# Mini_Control_Board.net
KiCad netlist of a schematic drawn in Altium Designer
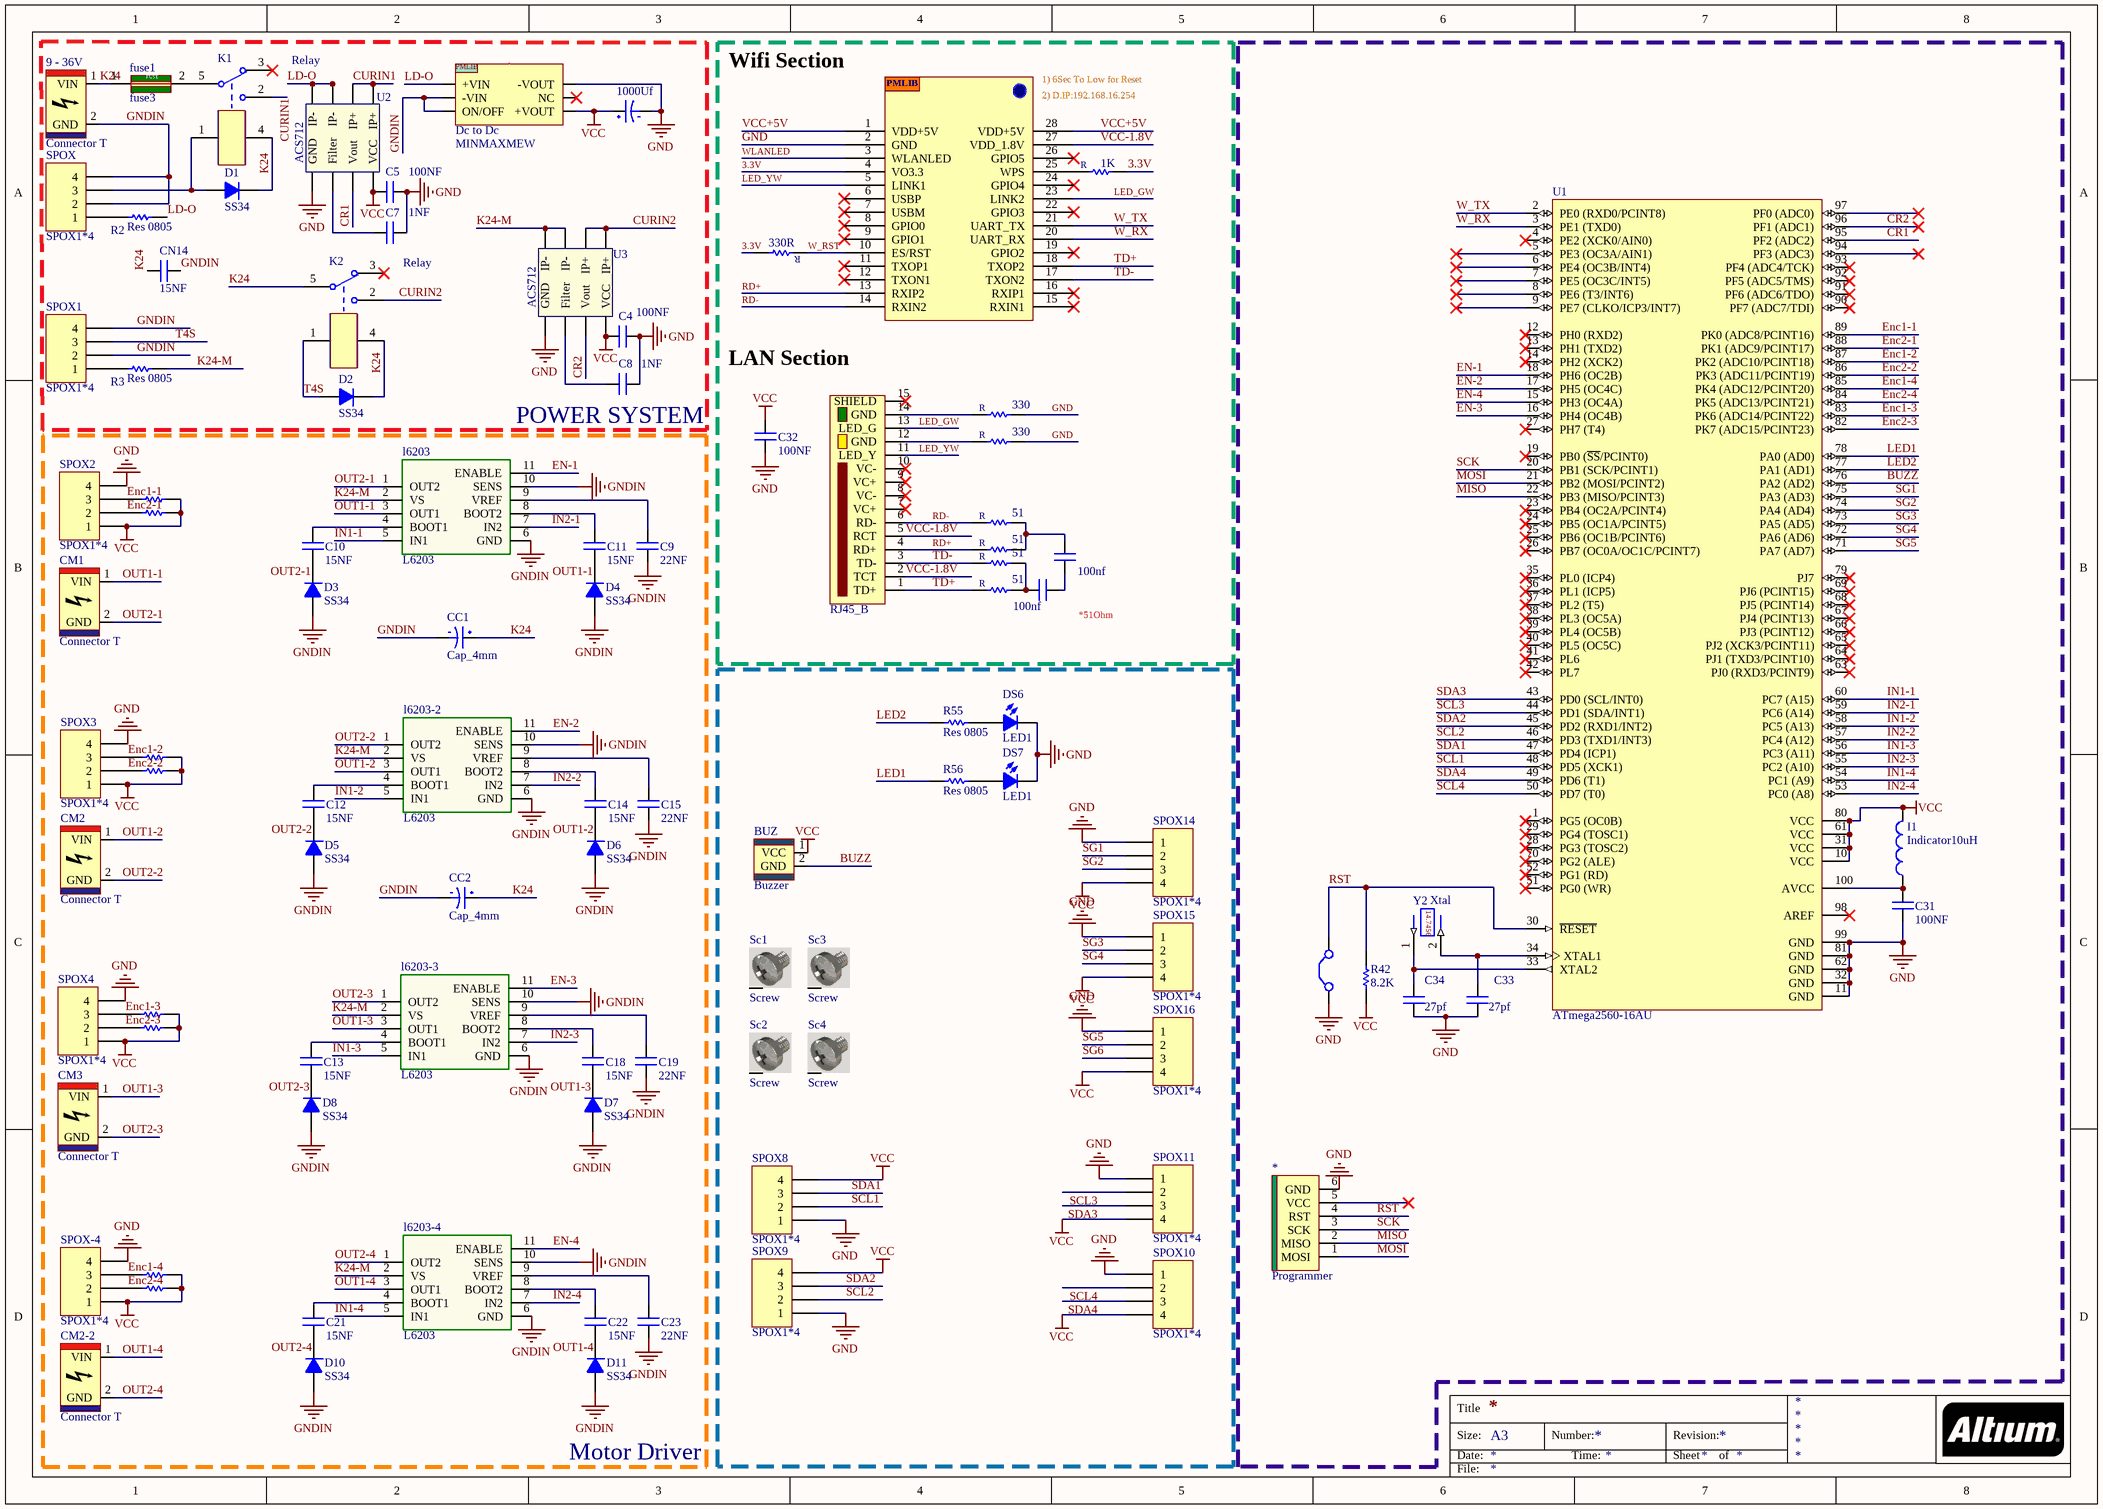
[diagram p0: Mini Control Board.SchDoc]

(export (version "E")
  (design (tool "Eeschema 10.0.6"))
  (components
    (comp (ref "*")
      (value "Programmer")
      (footprint "Programmer")
      (libsource (lib "PMLIB") (part "Programmer"))
    )
    (comp (ref "3") (value "HLK_WifiModule") (libsource (lib "PMLIB") (part "HLK_WifiModule")))
    (comp (ref "9 - 36V")
      (value "Connector T")
      (footprint "T_Connector")
      (libsource (lib "PMLIB") (part "Connector T"))
    )
    (comp (ref "34") (value "330") (footprint "R0805") (libsource (lib "PMLIB") (part "R0805")))
    (comp (ref "35") (value "330R") (footprint "R0805") (libsource (lib "PMLIB") (part "R0805")))
    (comp (ref "43") (value "330") (footprint "R0805") (libsource (lib "PMLIB") (part "R0805")))
    (comp (ref "89") (value "RJ45_B") (footprint "RJ45_B") (libsource (lib "PMLIB") (part "RJ45_B")))
    (comp (ref "1000Uf") (value "Cap_4mm") (footprint "Cap_4mm") (libsource (lib "PMLIB") (part "Cap_Pola")))
    (comp (ref "BUZ") (value "Buzzer") (footprint "Buzzer") (libsource (lib "PMLIB") (part "Buzzer")))
    (comp (ref "C4")
      (value "100NF")
      (footprint "Cap0805")
      (description "surface mount capacitor (size 805)")
      (libsource (lib "PMLIB") (part "Cap0805"))
    )
    (comp (ref "C5")
      (value "100NF")
      (footprint "Cap0805")
      (description "surface mount capacitor (size 805)")
      (libsource (lib "PMLIB") (part "Cap0805"))
    )
    (comp (ref "C7")
      (value "1NF")
      (footprint "Cap0805")
      (description "surface mount capacitor (size 805)")
      (libsource (lib "PMLIB") (part "Cap0805"))
    )
    (comp (ref "C8")
      (value "1NF")
      (footprint "Cap0805")
      (description "surface mount capacitor (size 805)")
      (libsource (lib "PMLIB") (part "Cap0805"))
    )
    (comp (ref "C9")
      (value "22NF")
      (footprint "Cap0805")
      (description "surface mount capacitor (size 805)")
      (libsource (lib "PMLIB") (part "Cap0805"))
    )
    (comp (ref "C10")
      (value "15NF")
      (footprint "Cap0805")
      (description "surface mount capacitor (size 805)")
      (libsource (lib "PMLIB") (part "Cap0805"))
    )
    (comp (ref "C11")
      (value "15NF")
      (footprint "Cap0805")
      (description "surface mount capacitor (size 805)")
      (libsource (lib "PMLIB") (part "Cap0805"))
    )
    (comp (ref "C12")
      (value "15NF")
      (footprint "Cap0805")
      (description "surface mount capacitor (size 805)")
      (libsource (lib "PMLIB") (part "Cap0805"))
    )
    (comp (ref "C13")
      (value "15NF")
      (footprint "Cap0805")
      (description "surface mount capacitor (size 805)")
      (libsource (lib "PMLIB") (part "Cap0805"))
    )
    (comp (ref "C14")
      (value "15NF")
      (footprint "Cap0805")
      (description "surface mount capacitor (size 805)")
      (libsource (lib "PMLIB") (part "Cap0805"))
    )
    (comp (ref "C15")
      (value "22NF")
      (footprint "Cap0805")
      (description "surface mount capacitor (size 805)")
      (libsource (lib "PMLIB") (part "Cap0805"))
    )
    (comp (ref "C18")
      (value "15NF")
      (footprint "Cap0805")
      (description "surface mount capacitor (size 805)")
      (libsource (lib "PMLIB") (part "Cap0805"))
    )
    (comp (ref "C19")
      (value "22NF")
      (footprint "Cap0805")
      (description "surface mount capacitor (size 805)")
      (libsource (lib "PMLIB") (part "Cap0805"))
    )
    (comp (ref "C21")
      (value "15NF")
      (footprint "Cap0805")
      (description "surface mount capacitor (size 805)")
      (libsource (lib "PMLIB") (part "Cap0805"))
    )
    (comp (ref "C22")
      (value "15NF")
      (footprint "Cap0805")
      (description "surface mount capacitor (size 805)")
      (libsource (lib "PMLIB") (part "Cap0805"))
    )
    (comp (ref "C23")
      (value "22NF")
      (footprint "Cap0805")
      (description "surface mount capacitor (size 805)")
      (libsource (lib "PMLIB") (part "Cap0805"))
    )
    (comp (ref "C31")
      (value "100NF")
      (footprint "Cap0805")
      (description "surface mount capacitor (size 805)")
      (libsource (lib "PMLIB") (part "Cap0805"))
    )
    (comp (ref "C32")
      (value "100NF")
      (footprint "Cap0805")
      (description "surface mount capacitor (size 805)")
      (libsource (lib "PMLIB") (part "Cap0805"))
    )
    (comp (ref "C33")
      (value "27pf")
      (footprint "Cap0805")
      (description "surface mount capacitor (size 805)")
      (libsource (lib "PMLIB") (part "Cap0805"))
    )
    (comp (ref "C34")
      (value "27pf")
      (footprint "Cap0805")
      (description "surface mount capacitor (size 805)")
      (libsource (lib "PMLIB") (part "Cap0805"))
    )
    (comp (ref "C93")
      (value "100nf")
      (footprint "Cap0805")
      (description "surface mount capacitor (size 805)")
      (libsource (lib "PMLIB") (part "Cap0805"))
    )
    (comp (ref "C94")
      (value "100nf")
      (footprint "Cap0805")
      (description "surface mount capacitor (size 805)")
      (libsource (lib "PMLIB") (part "Cap0805"))
    )
    (comp (ref "CC1") (value "Cap_4mm") (footprint "Cap_5mm") (libsource (lib "PMLIB") (part "Cap_Pola")))
    (comp (ref "CC2") (value "Cap_4mm") (footprint "Cap_5mm") (libsource (lib "PMLIB") (part "Cap_Pola")))
    (comp (ref "CM1")
      (value "Connector T")
      (footprint "T_Connector")
      (libsource (lib "PMLIB") (part "Connector T"))
    )
    (comp (ref "CM2")
      (value "Connector T")
      (footprint "T_Connector")
      (libsource (lib "PMLIB") (part "Connector T"))
    )
    (comp (ref "CM2-2")
      (value "Connector T")
      (footprint "T_Connector")
      (libsource (lib "PMLIB") (part "Connector T"))
    )
    (comp (ref "CM3")
      (value "Connector T")
      (footprint "T_Connector")
      (libsource (lib "PMLIB") (part "Connector T"))
    )
    (comp (ref "CN14")
      (value "15NF")
      (footprint "Cap0805")
      (description "surface mount capacitor (size 805)")
      (libsource (lib "PMLIB") (part "Cap0805"))
    )
    (comp (ref "D1") (value "SS34") (footprint "Diod-1A-SMD") (libsource (lib "PMLIB") (part "Diode")))
    (comp (ref "D2") (value "SS34") (footprint "Diod-1A-SMD") (libsource (lib "PMLIB") (part "Diode")))
    (comp (ref "D3") (value "SS34") (footprint "Diod-1A-SMD") (libsource (lib "PMLIB") (part "Diode")))
    (comp (ref "D4") (value "SS34") (footprint "Diod-1A-SMD") (libsource (lib "PMLIB") (part "Diode")))
    (comp (ref "D5") (value "SS34") (footprint "Diod-1A-SMD") (libsource (lib "PMLIB") (part "Diode")))
    (comp (ref "D6") (value "SS34") (footprint "Diod-1A-SMD") (libsource (lib "PMLIB") (part "Diode")))
    (comp (ref "D7") (value "SS34") (footprint "Diod-1A-SMD") (libsource (lib "PMLIB") (part "Diode")))
    (comp (ref "D8") (value "SS34") (footprint "Diod-1A-SMD") (libsource (lib "PMLIB") (part "Diode")))
    (comp (ref "D10") (value "SS34") (footprint "Diod-1A-SMD") (libsource (lib "PMLIB") (part "Diode")))
    (comp (ref "D11") (value "SS34") (footprint "Diod-1A-SMD") (libsource (lib "PMLIB") (part "Diode")))
    (comp (ref "Dc to Dc")
      (value "MINMAXMEW")
      (footprint "MINMAXMEW")
      (libsource (lib "PMLIB") (part "MINMAXMEW"))
    )
    (comp (ref "DS6") (value "LED1") (footprint "LED_SMD0805RED") (libsource (lib "PMLIB") (part "LED1")))
    (comp (ref "DS7") (value "LED1") (footprint "LED_SMD0805RED") (libsource (lib "PMLIB") (part "LED1")))
    (comp (ref "fdcg3") (value "Jumper") (footprint "Jumper") (libsource (lib "PMLIB") (part "Jumper")))
    (comp (ref "fuse1") (value "fuse3") (footprint "fuse_SMD0805") (libsource (lib "PMLIB") (part "fuse3")))
    (comp (ref "I1")
      (value "Indicator10uH")
      (footprint "1206")
      (libsource (lib "PMLIB") (part "Indicator100uH"))
    )
    (comp (ref "K1")
      (value "Relay")
      (footprint "RelayMilionMiniS-Z")
      (libsource (lib "PMLIB") (part "RelayMilon"))
    )
    (comp (ref "K2")
      (value "Relay")
      (footprint "RelayMilionMiniS-Z")
      (libsource (lib "PMLIB") (part "RelayMilon"))
    )
    (comp (ref "l6203") (value "L6203") (footprint "L6203") (libsource (lib "PMLIB") (part "L6203")))
    (comp (ref "l6203-2") (value "L6203") (footprint "L6203") (libsource (lib "PMLIB") (part "L6203")))
    (comp (ref "l6203-3") (value "L6203") (footprint "L6203") (libsource (lib "PMLIB") (part "L6203")))
    (comp (ref "l6203-4") (value "L6203") (footprint "L6203") (libsource (lib "PMLIB") (part "L6203")))
    (comp (ref "PO") (value "51") (footprint "R0805") (libsource (lib "PMLIB") (part "R0805")))
    (comp (ref "POS") (value "51") (footprint "R0805") (libsource (lib "PMLIB") (part "R0805")))
    (comp (ref "POS2") (value "51") (footprint "R0805") (libsource (lib "PMLIB") (part "R0805")))
    (comp (ref "POS3") (value "51") (footprint "R0805") (libsource (lib "PMLIB") (part "R0805")))
    (comp (ref "POSWW") (value "1K") (footprint "R0805") (libsource (lib "PMLIB") (part "R0805")))
    (comp (ref "R2") (value "Res 0805") (footprint "R0805") (libsource (lib "PMLIB") (part "Res 0805")))
    (comp (ref "R3") (value "Res 0805") (footprint "R0805") (libsource (lib "PMLIB") (part "Res 0805")))
    (comp (ref "R8") (value "Res 0805") (footprint "R0805") (libsource (lib "PMLIB") (part "Res 0805")))
    (comp (ref "R9") (value "Res 0805") (footprint "R0805") (libsource (lib "PMLIB") (part "Res 0805")))
    (comp (ref "R12") (value "Res 0805") (footprint "R0805") (libsource (lib "PMLIB") (part "Res 0805")))
    (comp (ref "R13") (value "Res 0805") (footprint "R0805") (libsource (lib "PMLIB") (part "Res 0805")))
    (comp (ref "R16") (value "Res 0805") (footprint "R0805") (libsource (lib "PMLIB") (part "Res 0805")))
    (comp (ref "R17") (value "Res 0805") (footprint "R0805") (libsource (lib "PMLIB") (part "Res 0805")))
    (comp (ref "R25") (value "Res 0805") (footprint "R0805") (libsource (lib "PMLIB") (part "Res 0805")))
    (comp (ref "r26") (value "Res 0805") (footprint "R0805") (libsource (lib "PMLIB") (part "Res 0805")))
    (comp (ref "R42") (value "8.2K") (footprint "R0805") (libsource (lib "PMLIB") (part "Res 0805")))
    (comp (ref "R55") (value "Res 0805") (footprint "R0805") (libsource (lib "PMLIB") (part "Res 0805")))
    (comp (ref "R56") (value "Res 0805") (footprint "R0805") (libsource (lib "PMLIB") (part "Res 0805")))
    (comp (ref "Sc1") (value "Screw") (footprint "Screw") (libsource (lib "PMLIB") (part "Screw")))
    (comp (ref "Sc2") (value "Screw") (footprint "Screw") (libsource (lib "PMLIB") (part "Screw")))
    (comp (ref "Sc3") (value "Screw") (footprint "Screw") (libsource (lib "PMLIB") (part "Screw")))
    (comp (ref "Sc4") (value "Screw") (footprint "Screw") (libsource (lib "PMLIB") (part "Screw")))
    (comp (ref "SPOX") (value "SPOX1*4") (footprint "SPOX_1*4RIGHT") (libsource (lib "") (part "SPOX1*4_1")))
    (comp (ref "SPOX-4")
      (value "SPOX1*4")
      (footprint "SPOX_1*4RIGHT")
      (libsource (lib "") (part "SPOX1*4_1"))
    )
    (comp (ref "SPOX1") (value "SPOX1*4") (footprint "SPOX_1*4RIGHT") (libsource (lib "") (part "SPOX1*4_1")))
    (comp (ref "SPOX2") (value "SPOX1*4") (footprint "SPOX_1*4RIGHT") (libsource (lib "") (part "SPOX1*4_1")))
    (comp (ref "SPOX3") (value "SPOX1*4") (footprint "SPOX_1*4RIGHT") (libsource (lib "") (part "SPOX1*4_1")))
    (comp (ref "SPOX4") (value "SPOX1*4") (footprint "SPOX_1*4RIGHT") (libsource (lib "") (part "SPOX1*4_1")))
    (comp (ref "SPOX8") (value "SPOX1*4") (footprint "SPOX_1*4RIGHT") (libsource (lib "") (part "SPOX1*4_1")))
    (comp (ref "SPOX9") (value "SPOX1*4") (footprint "SPOX_1*4RIGHT") (libsource (lib "") (part "SPOX1*4_1")))
    (comp (ref "SPOX10")
      (value "SPOX1*4")
      (footprint "SPOX_1*4RIGHT")
      (libsource (lib "PMLIB") (part "SPOX1*4"))
    )
    (comp (ref "SPOX11")
      (value "SPOX1*4")
      (footprint "SPOX_1*4RIGHT")
      (libsource (lib "PMLIB") (part "SPOX1*4"))
    )
    (comp (ref "SPOX14")
      (value "SPOX1*4")
      (footprint "SPOX_1*4RIGHT")
      (libsource (lib "PMLIB") (part "SPOX1*4"))
    )
    (comp (ref "SPOX15")
      (value "SPOX1*4")
      (footprint "SPOX_1*4RIGHT")
      (libsource (lib "PMLIB") (part "SPOX1*4"))
    )
    (comp (ref "SPOX16")
      (value "SPOX1*4")
      (footprint "SPOX_1*4RIGHT")
      (libsource (lib "PMLIB") (part "SPOX1*4"))
    )
    (comp (ref "U1")
      (value "ATmega2560-16AU")
      (footprint "100A_N")
      (libsource (lib "Atmel Microcontroller megaAVR") (part "ATmega2560-16AU"))
    )
    (comp (ref "U2")
      (value "ACS712")
      (footprint "SOP8")
      (description "Hall effect Current Sensor")
      (libsource (lib "PMLIB") (part "ACS712"))
    )
    (comp (ref "U3")
      (value "ACS712")
      (footprint "SOP8")
      (description "Hall effect Current Sensor")
      (libsource (lib "PMLIB") (part "ACS712"))
    )
    (comp (ref "Y2") (value "Xtal") (footprint "Crystal") (libsource (lib "PMLIB") (part "Crystal")))
  )
  (nets
    (net (code "1") (name "/3.3V") (class "Default")
      (node (ref "3") (pin "4") (pinfunction "VO3.3_4") (pintype "passive"))
      (node (ref "35") (pin "1") (pinfunction "1_1") (pintype "passive"))
      (node (ref "POSWW") (pin "1") (pinfunction "1_1") (pintype "passive"))
    )
    (net (code "2") (name "/BUZZ") (class "Default")
      (node (ref "BUZ") (pin "2") (pinfunction "GND_2") (pintype "passive"))
      (node (ref "U1") (pin "76") (pinfunction "PA2_(AD2)_76") (pintype "bidirectional"))
    )
    (net (code "3") (name "/CR1") (class "Default")
      (node (ref "U1") (pin "95") (pinfunction "PF2_(ADC2)_95") (pintype "bidirectional"))
      (node (ref "U2") (pin "7") (pinfunction "Vout_7") (pintype "passive"))
    )
    (net (code "4") (name "/CR2") (class "Default")
      (node (ref "U1") (pin "96") (pinfunction "PF1_(ADC1)_96") (pintype "bidirectional"))
      (node (ref "U3") (pin "7") (pinfunction "Vout_7") (pintype "passive"))
    )
    (net (code "5") (name "/CURIN1") (class "Default")
      (node (ref "K1") (pin "2") (pinfunction "2_2") (pintype "passive"))
      (node (ref "U2") (pin "1") (pinfunction "IP+_1") (pintype "passive"))
      (node (ref "U2") (pin "2") (pinfunction "IP+_2") (pintype "passive"))
    )
    (net (code "6") (name "/CURIN2") (class "Default")
      (node (ref "K2") (pin "2") (pinfunction "2_2") (pintype "passive"))
      (node (ref "U3") (pin "1") (pinfunction "IP+_1") (pintype "passive"))
      (node (ref "U3") (pin "2") (pinfunction "IP+_2") (pintype "passive"))
    )
    (net (code "7") (name "/EN-1") (class "Default")
      (node (ref "U1") (pin "18") (pinfunction "PH6_(OC2B)_18") (pintype "bidirectional"))
      (node (ref "l6203") (pin "11") (pinfunction "ENABLE_11") (pintype "passive"))
    )
    (net (code "8") (name "/EN-2") (class "Default")
      (node (ref "U1") (pin "17") (pinfunction "PH5_(OC4C)_17") (pintype "bidirectional"))
      (node (ref "l6203-2") (pin "11") (pinfunction "ENABLE_11") (pintype "passive"))
    )
    (net (code "9") (name "/EN-3") (class "Default")
      (node (ref "U1") (pin "16") (pinfunction "PH4_(OC4B)_16") (pintype "bidirectional"))
      (node (ref "l6203-3") (pin "11") (pinfunction "ENABLE_11") (pintype "passive"))
    )
    (net (code "10") (name "/EN-4") (class "Default")
      (node (ref "U1") (pin "15") (pinfunction "PH3_(OC4A)_15") (pintype "bidirectional"))
      (node (ref "l6203-4") (pin "11") (pinfunction "ENABLE_11") (pintype "passive"))
    )
    (net (code "11") (name "/Enc1-1") (class "Default")
      (node (ref "R8") (pin "2") (pinfunction "2_2") (pintype "passive"))
      (node (ref "SPOX2") (pin "3") (pinfunction "3_3") (pintype "passive"))
      (node (ref "U1") (pin "89") (pinfunction "PK0_(ADC8/PCINT16)_89") (pintype "bidirectional"))
    )
    (net (code "12") (name "/Enc1-2") (class "Default")
      (node (ref "R13") (pin "2") (pinfunction "2_2") (pintype "passive"))
      (node (ref "SPOX3") (pin "3") (pinfunction "3_3") (pintype "passive"))
      (node (ref "U1") (pin "87") (pinfunction "PK2_(ADC10/PCINT18)_87") (pintype "bidirectional"))
    )
    (net (code "13") (name "/Enc1-3") (class "Default")
      (node (ref "R16") (pin "2") (pinfunction "2_2") (pintype "passive"))
      (node (ref "SPOX4") (pin "3") (pinfunction "3_3") (pintype "passive"))
      (node (ref "U1") (pin "83") (pinfunction "PK6_(ADC14/PCINT22)_83") (pintype "bidirectional"))
    )
    (net (code "14") (name "/Enc1-4") (class "Default")
      (node (ref "R25") (pin "2") (pinfunction "2_2") (pintype "passive"))
      (node (ref "SPOX-4") (pin "3") (pinfunction "3_3") (pintype "passive"))
      (node (ref "U1") (pin "85") (pinfunction "PK4_(ADC12/PCINT20)_85") (pintype "bidirectional"))
    )
    (net (code "15") (name "/Enc2-1") (class "Default")
      (node (ref "R9") (pin "2") (pinfunction "2_2") (pintype "passive"))
      (node (ref "SPOX2") (pin "2") (pinfunction "2_2") (pintype "passive"))
      (node (ref "U1") (pin "88") (pinfunction "PK1_(ADC9/PCINT17)_88") (pintype "bidirectional"))
    )
    (net (code "16") (name "/Enc2-2") (class "Default")
      (node (ref "R12") (pin "2") (pinfunction "2_2") (pintype "passive"))
      (node (ref "SPOX3") (pin "2") (pinfunction "2_2") (pintype "passive"))
      (node (ref "U1") (pin "86") (pinfunction "PK3_(ADC11/PCINT19)_86") (pintype "bidirectional"))
    )
    (net (code "17") (name "/Enc2-3") (class "Default")
      (node (ref "R17") (pin "2") (pinfunction "2_2") (pintype "passive"))
      (node (ref "SPOX4") (pin "2") (pinfunction "2_2") (pintype "passive"))
      (node (ref "U1") (pin "82") (pinfunction "PK7_(ADC15/PCINT23)_82") (pintype "bidirectional"))
    )
    (net (code "18") (name "/Enc2-4") (class "Default")
      (node (ref "SPOX-4") (pin "2") (pinfunction "2_2") (pintype "passive"))
      (node (ref "U1") (pin "84") (pinfunction "PK5_(ADC13/PCINT21)_84") (pintype "bidirectional"))
      (node (ref "r26") (pin "2") (pinfunction "2_2") (pintype "passive"))
    )
    (net (code "19") (name "/IN1-1") (class "Default")
      (node (ref "U1") (pin "60") (pinfunction "PC7_(A15)_60") (pintype "bidirectional"))
      (node (ref "l6203") (pin "5") (pinfunction "IN1_5") (pintype "passive"))
    )
    (net (code "20") (name "/IN1-2") (class "Default")
      (node (ref "U1") (pin "58") (pinfunction "PC5_(A13)_58") (pintype "bidirectional"))
      (node (ref "l6203-2") (pin "5") (pinfunction "IN1_5") (pintype "passive"))
    )
    (net (code "21") (name "/IN1-3") (class "Default")
      (node (ref "U1") (pin "56") (pinfunction "PC3_(A11)_56") (pintype "bidirectional"))
      (node (ref "l6203-3") (pin "5") (pinfunction "IN1_5") (pintype "passive"))
    )
    (net (code "22") (name "/IN1-4") (class "Default")
      (node (ref "U1") (pin "54") (pinfunction "PC1_(A9)_54") (pintype "bidirectional"))
      (node (ref "l6203-4") (pin "5") (pinfunction "IN1_5") (pintype "passive"))
    )
    (net (code "23") (name "/IN2-1") (class "Default")
      (node (ref "U1") (pin "59") (pinfunction "PC6_(A14)_59") (pintype "bidirectional"))
      (node (ref "l6203") (pin "7") (pinfunction "IN2_7") (pintype "passive"))
    )
    (net (code "24") (name "/IN2-2") (class "Default")
      (node (ref "U1") (pin "57") (pinfunction "PC4_(A12)_57") (pintype "bidirectional"))
      (node (ref "l6203-2") (pin "7") (pinfunction "IN2_7") (pintype "passive"))
    )
    (net (code "25") (name "/IN2-3") (class "Default")
      (node (ref "U1") (pin "55") (pinfunction "PC2_(A10)_55") (pintype "bidirectional"))
      (node (ref "l6203-3") (pin "7") (pinfunction "IN2_7") (pintype "passive"))
    )
    (net (code "26") (name "/IN2-4") (class "Default")
      (node (ref "U1") (pin "53") (pinfunction "PC0_(A8)_53") (pintype "bidirectional"))
      (node (ref "l6203-4") (pin "7") (pinfunction "IN2_7") (pintype "passive"))
    )
    (net (code "27") (name "/K24") (class "Default")
      (node (ref "9 - 36V") (pin "1") (pinfunction "VIN_1") (pintype "passive"))
      (node (ref "CC1") (pin "2") (pinfunction "2_2") (pintype "passive"))
      (node (ref "CC2") (pin "2") (pinfunction "2_2") (pintype "passive"))
      (node (ref "CN14") (pin "1") (pinfunction "1_1") (pintype "passive"))
      (node (ref "D1") (pin "K") (pinfunction "K_K") (pintype "passive"))
      (node (ref "D2") (pin "K") (pinfunction "K_K") (pintype "passive"))
      (node (ref "K1") (pin "4") (pinfunction "4_4") (pintype "passive"))
      (node (ref "K2") (pin "4") (pinfunction "4_4") (pintype "passive"))
      (node (ref "K2") (pin "5") (pinfunction "5_5") (pintype "passive"))
      (node (ref "fuse1") (pin "1") (pinfunction "IN_1") (pintype "passive"))
    )
    (net (code "28") (name "/K24-M") (class "Default")
      (node (ref "R3") (pin "1") (pinfunction "1_1") (pintype "passive"))
      (node (ref "U3") (pin "3") (pinfunction "IP-_3") (pintype "passive"))
      (node (ref "U3") (pin "4") (pinfunction "IP-_4") (pintype "passive"))
      (node (ref "l6203") (pin "2") (pinfunction "VS_2") (pintype "passive"))
      (node (ref "l6203-2") (pin "2") (pinfunction "VS_2") (pintype "passive"))
      (node (ref "l6203-3") (pin "2") (pinfunction "VS_2") (pintype "passive"))
      (node (ref "l6203-4") (pin "2") (pinfunction "VS_2") (pintype "passive"))
    )
    (net (code "29") (name "/LD-O") (class "Default")
      (node (ref "Dc to Dc") (pin "2") (pinfunction "+VIN_2") (pintype "passive"))
      (node (ref "R2") (pin "1") (pinfunction "1_1") (pintype "passive"))
      (node (ref "U2") (pin "3") (pinfunction "IP-_3") (pintype "passive"))
      (node (ref "U2") (pin "4") (pinfunction "IP-_4") (pintype "passive"))
    )
    (net (code "30") (name "/LED1") (class "Default")
      (node (ref "R56") (pin "2") (pinfunction "2_2") (pintype "passive"))
      (node (ref "U1") (pin "78") (pinfunction "PA0_(AD0)_78") (pintype "bidirectional"))
    )
    (net (code "31") (name "/LED2") (class "Default")
      (node (ref "R55") (pin "2") (pinfunction "2_2") (pintype "passive"))
      (node (ref "U1") (pin "77") (pinfunction "PA1_(AD1)_77") (pintype "bidirectional"))
    )
    (net (code "32") (name "/LED_GW") (class "Default")
      (node (ref "3") (pin "23") (pinfunction "LINK2_23") (pintype "passive"))
      (node (ref "89") (pin "13") (pinfunction "LED_G_13") (pintype "passive"))
    )
    (net (code "33") (name "/LED_YW") (class "Default")
      (node (ref "3") (pin "5") (pinfunction "LINK1_5") (pintype "passive"))
      (node (ref "89") (pin "11") (pinfunction "LED_Y_11") (pintype "passive"))
    )
    (net (code "34") (name "/MISO") (class "Default")
      (node (ref "*") (pin "2") (pinfunction "MISO_2") (pintype "passive"))
      (node (ref "U1") (pin "22") (pinfunction "PB3_(MISO/PCINT3)_22") (pintype "bidirectional"))
    )
    (net (code "35") (name "/MOSI") (class "Default")
      (node (ref "*") (pin "1") (pinfunction "MOSI_1") (pintype "passive"))
      (node (ref "U1") (pin "21") (pinfunction "PB2_(MOSI/PCINT2)_21") (pintype "bidirectional"))
    )
    (net (code "36") (name "/OUT1-1") (class "Default")
      (node (ref "C11") (pin "2") (pinfunction "2_2") (pintype "passive"))
      (node (ref "CM1") (pin "1") (pinfunction "VIN_1") (pintype "passive"))
      (node (ref "D4") (pin "K") (pinfunction "K_K") (pintype "passive"))
      (node (ref "l6203") (pin "3") (pinfunction "OUT1_3") (pintype "passive"))
    )
    (net (code "37") (name "/OUT1-2") (class "Default")
      (node (ref "C14") (pin "2") (pinfunction "2_2") (pintype "passive"))
      (node (ref "CM2") (pin "1") (pinfunction "VIN_1") (pintype "passive"))
      (node (ref "D6") (pin "K") (pinfunction "K_K") (pintype "passive"))
      (node (ref "l6203-2") (pin "3") (pinfunction "OUT1_3") (pintype "passive"))
    )
    (net (code "38") (name "/OUT1-3") (class "Default")
      (node (ref "C18") (pin "2") (pinfunction "2_2") (pintype "passive"))
      (node (ref "CM3") (pin "1") (pinfunction "VIN_1") (pintype "passive"))
      (node (ref "D7") (pin "K") (pinfunction "K_K") (pintype "passive"))
      (node (ref "l6203-3") (pin "3") (pinfunction "OUT1_3") (pintype "passive"))
    )
    (net (code "39") (name "/OUT1-4") (class "Default")
      (node (ref "C22") (pin "2") (pinfunction "2_2") (pintype "passive"))
      (node (ref "CM2-2") (pin "1") (pinfunction "VIN_1") (pintype "passive"))
      (node (ref "D11") (pin "K") (pinfunction "K_K") (pintype "passive"))
      (node (ref "l6203-4") (pin "3") (pinfunction "OUT1_3") (pintype "passive"))
    )
    (net (code "40") (name "/OUT2-1") (class "Default")
      (node (ref "C10") (pin "2") (pinfunction "2_2") (pintype "passive"))
      (node (ref "CM1") (pin "2") (pinfunction "GND_2") (pintype "passive"))
      (node (ref "D3") (pin "K") (pinfunction "K_K") (pintype "passive"))
      (node (ref "l6203") (pin "1") (pinfunction "OUT2_1") (pintype "passive"))
    )
    (net (code "41") (name "/OUT2-2") (class "Default")
      (node (ref "C12") (pin "2") (pinfunction "2_2") (pintype "passive"))
      (node (ref "CM2") (pin "2") (pinfunction "GND_2") (pintype "passive"))
      (node (ref "D5") (pin "K") (pinfunction "K_K") (pintype "passive"))
      (node (ref "l6203-2") (pin "1") (pinfunction "OUT2_1") (pintype "passive"))
    )
    (net (code "42") (name "/OUT2-3") (class "Default")
      (node (ref "C13") (pin "2") (pinfunction "2_2") (pintype "passive"))
      (node (ref "CM3") (pin "2") (pinfunction "GND_2") (pintype "passive"))
      (node (ref "D8") (pin "K") (pinfunction "K_K") (pintype "passive"))
      (node (ref "l6203-3") (pin "1") (pinfunction "OUT2_1") (pintype "passive"))
    )
    (net (code "43") (name "/OUT2-4") (class "Default")
      (node (ref "C21") (pin "2") (pinfunction "2_2") (pintype "passive"))
      (node (ref "CM2-2") (pin "2") (pinfunction "GND_2") (pintype "passive"))
      (node (ref "D10") (pin "K") (pinfunction "K_K") (pintype "passive"))
      (node (ref "l6203-4") (pin "1") (pinfunction "OUT2_1") (pintype "passive"))
    )
    (net (code "44") (name "/RD+") (class "Default")
      (node (ref "3") (pin "13") (pinfunction "RXIP2_13") (pintype "passive"))
      (node (ref "89") (pin "4") (pinfunction "RD+_4") (pintype "passive"))
      (node (ref "POS3") (pin "2") (pinfunction "2_2") (pintype "passive"))
    )
    (net (code "45") (name "/RD-") (class "Default")
      (node (ref "3") (pin "14") (pinfunction "RXIN2_14") (pintype "passive"))
      (node (ref "89") (pin "6") (pinfunction "RD-_6") (pintype "passive"))
      (node (ref "POS2") (pin "2") (pinfunction "2_2") (pintype "passive"))
    )
    (net (code "46") (name "/RST") (class "Default")
      (node (ref "*") (pin "4") (pinfunction "RST_4") (pintype "passive"))
      (node (ref "R42") (pin "1") (pinfunction "1_1") (pintype "passive"))
      (node (ref "U1") (pin "30") (pinfunction "~{RESET}_30") (pintype "input"))
      (node (ref "fdcg3") (pin "2") (pinfunction "C2_2") (pintype "passive"))
    )
    (net (code "47") (name "/SCK") (class "Default")
      (node (ref "*") (pin "3") (pinfunction "SCK_3") (pintype "passive"))
      (node (ref "U1") (pin "20") (pinfunction "PB1_(SCK/PCINT1)_20") (pintype "bidirectional"))
    )
    (net (code "48") (name "/SCL1") (class "Default")
      (node (ref "SPOX8") (pin "2") (pinfunction "2_2") (pintype "passive"))
      (node (ref "U1") (pin "48") (pinfunction "PD5_(XCK1)_48") (pintype "bidirectional"))
    )
    (net (code "49") (name "/SCL2") (class "Default")
      (node (ref "SPOX9") (pin "2") (pinfunction "2_2") (pintype "passive"))
      (node (ref "U1") (pin "46") (pinfunction "PD3_(TXD1/INT3)_46") (pintype "bidirectional"))
    )
    (net (code "50") (name "/SCL3") (class "Default")
      (node (ref "SPOX11") (pin "2") (pinfunction "2_2") (pintype "passive"))
      (node (ref "U1") (pin "44") (pinfunction "PD1_(SDA/INT1)_44") (pintype "bidirectional"))
    )
    (net (code "51") (name "/SCL4") (class "Default")
      (node (ref "SPOX10") (pin "2") (pinfunction "2_2") (pintype "passive"))
      (node (ref "U1") (pin "50") (pinfunction "PD7_(T0)_50") (pintype "bidirectional"))
    )
    (net (code "52") (name "/SDA1") (class "Default")
      (node (ref "SPOX8") (pin "3") (pinfunction "3_3") (pintype "passive"))
      (node (ref "U1") (pin "47") (pinfunction "PD4_(ICP1)_47") (pintype "bidirectional"))
    )
    (net (code "53") (name "/SDA2") (class "Default")
      (node (ref "SPOX9") (pin "3") (pinfunction "3_3") (pintype "passive"))
      (node (ref "U1") (pin "45") (pinfunction "PD2_(RXD1/INT2)_45") (pintype "bidirectional"))
    )
    (net (code "54") (name "/SDA3") (class "Default")
      (node (ref "SPOX11") (pin "3") (pinfunction "3_3") (pintype "passive"))
      (node (ref "U1") (pin "43") (pinfunction "PD0_(SCL/INT0)_43") (pintype "bidirectional"))
    )
    (net (code "55") (name "/SDA4") (class "Default")
      (node (ref "SPOX10") (pin "3") (pinfunction "3_3") (pintype "passive"))
      (node (ref "U1") (pin "49") (pinfunction "PD6_(T1)_49") (pintype "bidirectional"))
    )
    (net (code "56") (name "/SG1") (class "Default")
      (node (ref "SPOX14") (pin "2") (pinfunction "2_2") (pintype "passive"))
      (node (ref "U1") (pin "75") (pinfunction "PA3_(AD3)_75") (pintype "bidirectional"))
    )
    (net (code "57") (name "/SG2") (class "Default")
      (node (ref "SPOX14") (pin "3") (pinfunction "3_3") (pintype "passive"))
      (node (ref "U1") (pin "74") (pinfunction "PA4_(AD4)_74") (pintype "bidirectional"))
    )
    (net (code "58") (name "/SG3") (class "Default")
      (node (ref "SPOX15") (pin "2") (pinfunction "2_2") (pintype "passive"))
      (node (ref "U1") (pin "73") (pinfunction "PA5_(AD5)_73") (pintype "bidirectional"))
    )
    (net (code "59") (name "/SG4") (class "Default")
      (node (ref "SPOX15") (pin "3") (pinfunction "3_3") (pintype "passive"))
      (node (ref "U1") (pin "72") (pinfunction "PA6_(AD6)_72") (pintype "bidirectional"))
    )
    (net (code "60") (name "/SG5") (class "Default")
      (node (ref "SPOX16") (pin "2") (pinfunction "2_2") (pintype "passive"))
      (node (ref "U1") (pin "71") (pinfunction "PA7_(AD7)_71") (pintype "bidirectional"))
    )
    (net (code "61") (name "/SG6") (class "Default")
      (node (ref "SPOX16") (pin "3") (pinfunction "3_3") (pintype "passive"))
    )
    (net (code "62") (name "/T4S") (class "Default")
      (node (ref "D2") (pin "A") (pinfunction "A_A") (pintype "passive"))
      (node (ref "K2") (pin "1") (pinfunction "1_1") (pintype "passive"))
      (node (ref "SPOX1") (pin "3") (pinfunction "3_3") (pintype "passive"))
    )
    (net (code "63") (name "/TD+") (class "Default")
      (node (ref "3") (pin "18") (pinfunction "TXOP2_18") (pintype "passive"))
      (node (ref "89") (pin "1") (pinfunction "TD+_1") (pintype "passive"))
      (node (ref "PO") (pin "2") (pinfunction "2_2") (pintype "passive"))
    )
    (net (code "64") (name "/TD-") (class "Default")
      (node (ref "3") (pin "17") (pinfunction "TXON2_17") (pintype "passive"))
      (node (ref "89") (pin "3") (pinfunction "TD-_3") (pintype "passive"))
      (node (ref "POS") (pin "2") (pinfunction "2_2") (pintype "passive"))
    )
    (net (code "65") (name "/VCC+5V") (class "Default")
      (node (ref "3") (pin "1") (pinfunction "VDD+5V_1") (pintype "passive"))
      (node (ref "3") (pin "28") (pinfunction "VDD+5V_28") (pintype "passive"))
    )
    (net (code "66") (name "/VCC-1.8V") (class "Default")
      (node (ref "3") (pin "27") (pinfunction "VDD_1.8V_27") (pintype "passive"))
      (node (ref "89") (pin "2") (pinfunction "TCT_2") (pintype "passive"))
      (node (ref "89") (pin "5") (pinfunction "RCT_5") (pintype "passive"))
    )
    (net (code "67") (name "/WLANLED") (class "Default")
      (node (ref "3") (pin "3") (pinfunction "WLANLED_3") (pintype "passive"))
    )
    (net (code "68") (name "/W_RST") (class "Default")
      (node (ref "3") (pin "10") (pinfunction "ES/RST_10") (pintype "passive"))
      (node (ref "35") (pin "2") (pinfunction "2_2") (pintype "passive"))
    )
    (net (code "69") (name "/W_RX") (class "Default")
      (node (ref "3") (pin "20") (pinfunction "UART_RX_20") (pintype "passive"))
      (node (ref "U1") (pin "3") (pinfunction "PE1_(TXD0)_3") (pintype "bidirectional"))
    )
    (net (code "70") (name "/W_TX") (class "Default")
      (node (ref "3") (pin "21") (pinfunction "UART_TX_21") (pintype "passive"))
      (node (ref "U1") (pin "2") (pinfunction "PE0_(RXD0/PCINT8)_2") (pintype "bidirectional"))
    )
    (net (code "71") (name "GND") (class "Default")
      (node (ref "*") (pin "6") (pinfunction "GND_6") (pintype "passive"))
      (node (ref "1000Uf") (pin "1") (pinfunction "1_1") (pintype "passive"))
      (node (ref "3") (pin "2") (pinfunction "GND_2") (pintype "passive"))
      (node (ref "34") (pin "1") (pinfunction "1_1") (pintype "passive"))
      (node (ref "43") (pin "1") (pinfunction "1_1") (pintype "passive"))
      (node (ref "C31") (pin "1") (pinfunction "1_1") (pintype "passive"))
      (node (ref "C32") (pin "1") (pinfunction "1_1") (pintype "passive"))
      (node (ref "C33") (pin "1") (pinfunction "1_1") (pintype "passive"))
      (node (ref "C34") (pin "1") (pinfunction "1_1") (pintype "passive"))
      (node (ref "C4") (pin "2") (pinfunction "2_2") (pintype "passive"))
      (node (ref "C5") (pin "2") (pinfunction "2_2") (pintype "passive"))
      (node (ref "C7") (pin "2") (pinfunction "2_2") (pintype "passive"))
      (node (ref "C8") (pin "2") (pinfunction "2_2") (pintype "passive"))
      (node (ref "DS6") (pin "K") (pinfunction "K_K") (pintype "passive"))
      (node (ref "DS7") (pin "K") (pinfunction "K_K") (pintype "passive"))
      (node (ref "Dc to Dc") (pin "7") (pinfunction "-VOUT_7") (pintype "passive"))
      (node (ref "SPOX-4") (pin "4") (pinfunction "4_4") (pintype "passive"))
      (node (ref "SPOX10") (pin "1") (pinfunction "1_1") (pintype "passive"))
      (node (ref "SPOX11") (pin "1") (pinfunction "1_1") (pintype "passive"))
      (node (ref "SPOX14") (pin "1") (pinfunction "1_1") (pintype "passive"))
      (node (ref "SPOX15") (pin "1") (pinfunction "1_1") (pintype "passive"))
      (node (ref "SPOX16") (pin "1") (pinfunction "1_1") (pintype "passive"))
      (node (ref "SPOX2") (pin "4") (pinfunction "4_4") (pintype "passive"))
      (node (ref "SPOX3") (pin "4") (pinfunction "4_4") (pintype "passive"))
      (node (ref "SPOX4") (pin "4") (pinfunction "4_4") (pintype "passive"))
      (node (ref "SPOX8") (pin "1") (pinfunction "1_1") (pintype "passive"))
      (node (ref "SPOX9") (pin "1") (pinfunction "1_1") (pintype "passive"))
      (node (ref "U1") (pin "11") (pinfunction "GND_11") (pintype "power_in"))
      (node (ref "U1") (pin "32") (pinfunction "GND_32") (pintype "power_in"))
      (node (ref "U1") (pin "62") (pinfunction "GND_62") (pintype "power_in"))
      (node (ref "U1") (pin "81") (pinfunction "GND_81") (pintype "power_in"))
      (node (ref "U1") (pin "99") (pinfunction "GND_99") (pintype "power_in"))
      (node (ref "U2") (pin "5") (pinfunction "GND_5") (pintype "passive"))
      (node (ref "U3") (pin "5") (pinfunction "GND_5") (pintype "passive"))
      (node (ref "fdcg3") (pin "1") (pinfunction "C1_1") (pintype "passive"))
    )
    (net (code "72") (name "GNDIN") (class "Default")
      (node (ref "9 - 36V") (pin "2") (pinfunction "GND_2") (pintype "passive"))
      (node (ref "C15") (pin "2") (pinfunction "2_2") (pintype "passive"))
      (node (ref "C19") (pin "2") (pinfunction "2_2") (pintype "passive"))
      (node (ref "C23") (pin "2") (pinfunction "2_2") (pintype "passive"))
      (node (ref "C9") (pin "2") (pinfunction "2_2") (pintype "passive"))
      (node (ref "CC1") (pin "1") (pinfunction "1_1") (pintype "passive"))
      (node (ref "CC2") (pin "1") (pinfunction "1_1") (pintype "passive"))
      (node (ref "CN14") (pin "2") (pinfunction "2_2") (pintype "passive"))
      (node (ref "D10") (pin "A") (pinfunction "A_A") (pintype "passive"))
      (node (ref "D11") (pin "A") (pinfunction "A_A") (pintype "passive"))
      (node (ref "D3") (pin "A") (pinfunction "A_A") (pintype "passive"))
      (node (ref "D4") (pin "A") (pinfunction "A_A") (pintype "passive"))
      (node (ref "D5") (pin "A") (pinfunction "A_A") (pintype "passive"))
      (node (ref "D6") (pin "A") (pinfunction "A_A") (pintype "passive"))
      (node (ref "D7") (pin "A") (pinfunction "A_A") (pintype "passive"))
      (node (ref "D8") (pin "A") (pinfunction "A_A") (pintype "passive"))
      (node (ref "Dc to Dc") (pin "1") (pinfunction "-VIN_1") (pintype "passive"))
      (node (ref "Dc to Dc") (pin "3") (pinfunction "ON/OFF_3") (pintype "passive"))
      (node (ref "SPOX") (pin "2") (pinfunction "2_2") (pintype "passive"))
      (node (ref "SPOX") (pin "4") (pinfunction "4_4") (pintype "passive"))
      (node (ref "SPOX1") (pin "2") (pinfunction "2_2") (pintype "passive"))
      (node (ref "SPOX1") (pin "4") (pinfunction "4_4") (pintype "passive"))
      (node (ref "l6203") (pin "10") (pinfunction "SENS_10") (pintype "passive"))
      (node (ref "l6203") (pin "6") (pinfunction "GND_6") (pintype "passive"))
      (node (ref "l6203-2") (pin "10") (pinfunction "SENS_10") (pintype "passive"))
      (node (ref "l6203-2") (pin "6") (pinfunction "GND_6") (pintype "passive"))
      (node (ref "l6203-3") (pin "10") (pinfunction "SENS_10") (pintype "passive"))
      (node (ref "l6203-3") (pin "6") (pinfunction "GND_6") (pintype "passive"))
      (node (ref "l6203-4") (pin "10") (pinfunction "SENS_10") (pintype "passive"))
      (node (ref "l6203-4") (pin "6") (pinfunction "GND_6") (pintype "passive"))
    )
    (net (code "73") (name "Net-(3-WPS)") (class "Default")
      (node (ref "3") (pin "25") (pinfunction "WPS_25") (pintype "passive"))
      (node (ref "POSWW") (pin "2") (pinfunction "2_2") (pintype "passive"))
    )
    (net (code "74") (name "Net-(34-Pad2)") (class "Default")
      (node (ref "34") (pin "2") (pinfunction "2_2") (pintype "passive"))
      (node (ref "89") (pin "14") (pinfunction "GND_14") (pintype "passive"))
    )
    (net (code "75") (name "Net-(43-Pad2)") (class "Default")
      (node (ref "43") (pin "2") (pinfunction "2_2") (pintype "passive"))
      (node (ref "89") (pin "12") (pinfunction "GND_12") (pintype "passive"))
    )
    (net (code "76") (name "Net-(C93-Pad1)") (class "Default")
      (node (ref "C93") (pin "1") (pinfunction "1_1") (pintype "passive"))
      (node (ref "C94") (pin "1") (pinfunction "1_1") (pintype "passive"))
    )
    (net (code "77") (name "Net-(C93-Pad2)") (class "Default")
      (node (ref "C93") (pin "2") (pinfunction "2_2") (pintype "passive"))
      (node (ref "PO") (pin "1") (pinfunction "1_1") (pintype "passive"))
      (node (ref "POS") (pin "1") (pinfunction "1_1") (pintype "passive"))
    )
    (net (code "78") (name "Net-(C94-Pad2)") (class "Default")
      (node (ref "C94") (pin "2") (pinfunction "2_2") (pintype "passive"))
      (node (ref "POS2") (pin "1") (pinfunction "1_1") (pintype "passive"))
      (node (ref "POS3") (pin "1") (pinfunction "1_1") (pintype "passive"))
    )
    (net (code "79") (name "Net-(D1-PadA)") (class "Default")
      (node (ref "D1") (pin "A") (pinfunction "A_A") (pintype "passive"))
      (node (ref "K1") (pin "1") (pinfunction "1_1") (pintype "passive"))
      (node (ref "SPOX") (pin "3") (pinfunction "3_3") (pintype "passive"))
    )
    (net (code "80") (name "Net-(DS6-PadA)") (class "Default")
      (node (ref "DS6") (pin "A") (pinfunction "A_A") (pintype "passive"))
      (node (ref "R55") (pin "1") (pinfunction "1_1") (pintype "passive"))
    )
    (net (code "81") (name "Net-(DS7-PadA)") (class "Default")
      (node (ref "DS7") (pin "A") (pinfunction "A_A") (pintype "passive"))
      (node (ref "R56") (pin "1") (pinfunction "1_1") (pintype "passive"))
    )
    (net (code "82") (name "Net-(R2-Pad2)") (class "Default")
      (node (ref "R2") (pin "2") (pinfunction "2_2") (pintype "passive"))
      (node (ref "SPOX") (pin "1") (pinfunction "1_1") (pintype "passive"))
    )
    (net (code "83") (name "Net-(R3-Pad2)") (class "Default")
      (node (ref "R3") (pin "2") (pinfunction "2_2") (pintype "passive"))
      (node (ref "SPOX1") (pin "1") (pinfunction "1_1") (pintype "passive"))
    )
    (net (code "84") (name "Net-(U1-AVCC)") (class "Default")
      (node (ref "C31") (pin "2") (pinfunction "2_2") (pintype "passive"))
      (node (ref "I1") (pin "1") (pinfunction "1_1") (pintype "passive"))
      (node (ref "U1") (pin "100") (pinfunction "AVCC_100") (pintype "power_in"))
    )
    (net (code "85") (name "Net-(U1-XTAL1)") (class "Default")
      (node (ref "C33") (pin "2") (pinfunction "2_2") (pintype "passive"))
      (node (ref "U1") (pin "34") (pinfunction "XTAL1_34") (pintype "input"))
      (node (ref "Y2") (pin "2") (pinfunction "2_2") (pintype "input"))
    )
    (net (code "86") (name "Net-(U1-XTAL2)") (class "Default")
      (node (ref "C34") (pin "2") (pinfunction "2_2") (pintype "passive"))
      (node (ref "U1") (pin "33") (pinfunction "XTAL2_33") (pintype "output"))
      (node (ref "Y2") (pin "1") (pinfunction "1_1") (pintype "output"))
    )
    (net (code "87") (name "Net-(U2-Filter)") (class "Default")
      (node (ref "C7") (pin "1") (pinfunction "1_1") (pintype "passive"))
      (node (ref "U2") (pin "6") (pinfunction "Filter_6") (pintype "passive"))
    )
    (net (code "88") (name "Net-(U3-Filter)") (class "Default")
      (node (ref "C8") (pin "1") (pinfunction "1_1") (pintype "passive"))
      (node (ref "U3") (pin "6") (pinfunction "Filter_6") (pintype "passive"))
    )
    (net (code "89") (name "Net-(fuse1-OUT)") (class "Default")
      (node (ref "K1") (pin "5") (pinfunction "5_5") (pintype "passive"))
      (node (ref "fuse1") (pin "2") (pinfunction "OUT_2") (pintype "passive"))
    )
    (net (code "90") (name "Net-(l6203-2-BOOT1)") (class "Default")
      (node (ref "C12") (pin "1") (pinfunction "1_1") (pintype "passive"))
      (node (ref "l6203-2") (pin "4") (pinfunction "BOOT1_4") (pintype "passive"))
    )
    (net (code "91") (name "Net-(l6203-2-BOOT2)") (class "Default")
      (node (ref "C14") (pin "1") (pinfunction "1_1") (pintype "passive"))
      (node (ref "l6203-2") (pin "8") (pinfunction "BOOT2_8") (pintype "passive"))
    )
    (net (code "92") (name "Net-(l6203-2-VREF)") (class "Default")
      (node (ref "C15") (pin "1") (pinfunction "1_1") (pintype "passive"))
      (node (ref "l6203-2") (pin "9") (pinfunction "VREF_9") (pintype "passive"))
    )
    (net (code "93") (name "Net-(l6203-3-BOOT1)") (class "Default")
      (node (ref "C13") (pin "1") (pinfunction "1_1") (pintype "passive"))
      (node (ref "l6203-3") (pin "4") (pinfunction "BOOT1_4") (pintype "passive"))
    )
    (net (code "94") (name "Net-(l6203-3-BOOT2)") (class "Default")
      (node (ref "C18") (pin "1") (pinfunction "1_1") (pintype "passive"))
      (node (ref "l6203-3") (pin "8") (pinfunction "BOOT2_8") (pintype "passive"))
    )
    (net (code "95") (name "Net-(l6203-3-VREF)") (class "Default")
      (node (ref "C19") (pin "1") (pinfunction "1_1") (pintype "passive"))
      (node (ref "l6203-3") (pin "9") (pinfunction "VREF_9") (pintype "passive"))
    )
    (net (code "96") (name "Net-(l6203-4-BOOT1)") (class "Default")
      (node (ref "C21") (pin "1") (pinfunction "1_1") (pintype "passive"))
      (node (ref "l6203-4") (pin "4") (pinfunction "BOOT1_4") (pintype "passive"))
    )
    (net (code "97") (name "Net-(l6203-4-BOOT2)") (class "Default")
      (node (ref "C22") (pin "1") (pinfunction "1_1") (pintype "passive"))
      (node (ref "l6203-4") (pin "8") (pinfunction "BOOT2_8") (pintype "passive"))
    )
    (net (code "98") (name "Net-(l6203-4-VREF)") (class "Default")
      (node (ref "C23") (pin "1") (pinfunction "1_1") (pintype "passive"))
      (node (ref "l6203-4") (pin "9") (pinfunction "VREF_9") (pintype "passive"))
    )
    (net (code "99") (name "Net-(l6203-BOOT1)") (class "Default")
      (node (ref "C10") (pin "1") (pinfunction "1_1") (pintype "passive"))
      (node (ref "l6203") (pin "4") (pinfunction "BOOT1_4") (pintype "passive"))
    )
    (net (code "100") (name "Net-(l6203-BOOT2)") (class "Default")
      (node (ref "C11") (pin "1") (pinfunction "1_1") (pintype "passive"))
      (node (ref "l6203") (pin "8") (pinfunction "BOOT2_8") (pintype "passive"))
    )
    (net (code "101") (name "Net-(l6203-VREF)") (class "Default")
      (node (ref "C9") (pin "1") (pinfunction "1_1") (pintype "passive"))
      (node (ref "l6203") (pin "9") (pinfunction "VREF_9") (pintype "passive"))
    )
    (net (code "102") (name "VCC") (class "Default")
      (node (ref "1000Uf") (pin "2") (pinfunction "2_2") (pintype "passive"))
      (node (ref "BUZ") (pin "1") (pinfunction "VCC_1") (pintype "passive"))
      (node (ref "C32") (pin "2") (pinfunction "2_2") (pintype "passive"))
      (node (ref "C4") (pin "1") (pinfunction "1_1") (pintype "passive"))
      (node (ref "C5") (pin "1") (pinfunction "1_1") (pintype "passive"))
      (node (ref "Dc to Dc") (pin "6") (pinfunction "+VOUT_6") (pintype "passive"))
      (node (ref "I1") (pin "2") (pinfunction "2_2") (pintype "passive"))
      (node (ref "R12") (pin "1") (pinfunction "1_1") (pintype "passive"))
      (node (ref "R13") (pin "1") (pinfunction "1_1") (pintype "passive"))
      (node (ref "R16") (pin "1") (pinfunction "1_1") (pintype "passive"))
      (node (ref "R17") (pin "1") (pinfunction "1_1") (pintype "passive"))
      (node (ref "R25") (pin "1") (pinfunction "1_1") (pintype "passive"))
      (node (ref "R42") (pin "2") (pinfunction "2_2") (pintype "passive"))
      (node (ref "R8") (pin "1") (pinfunction "1_1") (pintype "passive"))
      (node (ref "R9") (pin "1") (pinfunction "1_1") (pintype "passive"))
      (node (ref "SPOX-4") (pin "1") (pinfunction "1_1") (pintype "passive"))
      (node (ref "SPOX10") (pin "4") (pinfunction "4_4") (pintype "passive"))
      (node (ref "SPOX11") (pin "4") (pinfunction "4_4") (pintype "passive"))
      (node (ref "SPOX14") (pin "4") (pinfunction "4_4") (pintype "passive"))
      (node (ref "SPOX15") (pin "4") (pinfunction "4_4") (pintype "passive"))
      (node (ref "SPOX16") (pin "4") (pinfunction "4_4") (pintype "passive"))
      (node (ref "SPOX2") (pin "1") (pinfunction "1_1") (pintype "passive"))
      (node (ref "SPOX3") (pin "1") (pinfunction "1_1") (pintype "passive"))
      (node (ref "SPOX4") (pin "1") (pinfunction "1_1") (pintype "passive"))
      (node (ref "SPOX8") (pin "4") (pinfunction "4_4") (pintype "passive"))
      (node (ref "SPOX9") (pin "4") (pinfunction "4_4") (pintype "passive"))
      (node (ref "U1") (pin "10") (pinfunction "VCC_10") (pintype "power_in"))
      (node (ref "U1") (pin "31") (pinfunction "VCC_31") (pintype "power_in"))
      (node (ref "U1") (pin "61") (pinfunction "VCC_61") (pintype "power_in"))
      (node (ref "U1") (pin "80") (pinfunction "VCC_80") (pintype "power_in"))
      (node (ref "U2") (pin "8") (pinfunction "VCC_8") (pintype "passive"))
      (node (ref "U3") (pin "8") (pinfunction "VCC_8") (pintype "passive"))
      (node (ref "r26") (pin "1") (pinfunction "1_1") (pintype "passive"))
    )
    (net (code "103") (name "unconnected-(*-VCC-Pad5)") (class "Default")
      (node (ref "*") (pin "5") (pinfunction "VCC_5") (pintype "passive+no_connect"))
    )
    (net (code "104") (name "unconnected-(3-GPIO0-Pad8)") (class "Default")
      (node (ref "3") (pin "8") (pinfunction "GPIO0_8") (pintype "passive+no_connect"))
    )
    (net (code "105") (name "unconnected-(3-GPIO1-Pad9)") (class "Default")
      (node (ref "3") (pin "9") (pinfunction "GPIO1_9") (pintype "passive+no_connect"))
    )
    (net (code "106") (name "unconnected-(3-GPIO2-Pad19)") (class "Default")
      (node (ref "3") (pin "19") (pinfunction "GPIO2_19") (pintype "passive+no_connect"))
    )
    (net (code "107") (name "unconnected-(3-GPIO3-Pad22)") (class "Default")
      (node (ref "3") (pin "22") (pinfunction "GPIO3_22") (pintype "passive+no_connect"))
    )
    (net (code "108") (name "unconnected-(3-GPIO4-Pad24)") (class "Default")
      (node (ref "3") (pin "24") (pinfunction "GPIO4_24") (pintype "passive+no_connect"))
    )
    (net (code "109") (name "unconnected-(3-GPIO5-Pad26)") (class "Default")
      (node (ref "3") (pin "26") (pinfunction "GPIO5_26") (pintype "passive+no_connect"))
    )
    (net (code "110") (name "unconnected-(3-RXIN1-Pad15)") (class "Default")
      (node (ref "3") (pin "15") (pinfunction "RXIN1_15") (pintype "passive+no_connect"))
    )
    (net (code "111") (name "unconnected-(3-RXIP1-Pad16)") (class "Default")
      (node (ref "3") (pin "16") (pinfunction "RXIP1_16") (pintype "passive+no_connect"))
    )
    (net (code "112") (name "unconnected-(3-TXON1-Pad12)") (class "Default")
      (node (ref "3") (pin "12") (pinfunction "TXON1_12") (pintype "passive+no_connect"))
    )
    (net (code "113") (name "unconnected-(3-TXOP1-Pad11)") (class "Default")
      (node (ref "3") (pin "11") (pinfunction "TXOP1_11") (pintype "passive+no_connect"))
    )
    (net (code "114") (name "unconnected-(3-USBM-Pad7)") (class "Default")
      (node (ref "3") (pin "7") (pinfunction "USBM_7") (pintype "passive+no_connect"))
    )
    (net (code "115") (name "unconnected-(3-USBP-Pad6)") (class "Default")
      (node (ref "3") (pin "6") (pinfunction "USBP_6") (pintype "passive+no_connect"))
    )
    (net (code "116") (name "unconnected-(89-SHIELD-Pad15)") (class "Default")
      (node (ref "89") (pin "15") (pinfunction "SHIELD_15") (pintype "passive+no_connect"))
    )
    (net (code "117") (name "unconnected-(89-VC+-Pad7)") (class "Default")
      (node (ref "89") (pin "7") (pinfunction "VC+_7") (pintype "passive+no_connect"))
    )
    (net (code "118") (name "unconnected-(89-VC+-Pad9)") (class "Default")
      (node (ref "89") (pin "9") (pinfunction "VC+_9") (pintype "passive+no_connect"))
    )
    (net (code "119") (name "unconnected-(89-VC--Pad8)") (class "Default")
      (node (ref "89") (pin "8") (pinfunction "VC-_8") (pintype "passive+no_connect"))
    )
    (net (code "120") (name "unconnected-(89-VC--Pad10)") (class "Default")
      (node (ref "89") (pin "10") (pinfunction "VC-_10") (pintype "passive+no_connect"))
    )
    (net (code "121") (name "unconnected-(Dc to Dc-NC-Pad5)") (class "Default")
      (node (ref "Dc to Dc") (pin "5") (pinfunction "NC_5") (pintype "passive+no_connect"))
    )
    (net (code "122") (name "unconnected-(Dc to Dc-NC-Pad8)") (class "Default")
      (node (ref "Dc to Dc") (pin "8") (pinfunction "NC_8") (pintype "passive"))
    )
    (net (code "123") (name "unconnected-(K1-Pad3)") (class "Default")
      (node (ref "K1") (pin "3") (pinfunction "3_3") (pintype "passive+no_connect"))
    )
    (net (code "124") (name "unconnected-(K2-Pad3)") (class "Default")
      (node (ref "K2") (pin "3") (pinfunction "3_3") (pintype "passive+no_connect"))
    )
    (net (code "125") (name "unconnected-(Sc1-PadS)") (class "Default")
      (node (ref "Sc1") (pin "S") (pinfunction "S_S") (pintype "passive"))
    )
    (net (code "126") (name "unconnected-(Sc2-PadS)") (class "Default")
      (node (ref "Sc2") (pin "S") (pinfunction "S_S") (pintype "passive"))
    )
    (net (code "127") (name "unconnected-(Sc3-PadS)") (class "Default")
      (node (ref "Sc3") (pin "S") (pinfunction "S_S") (pintype "passive"))
    )
    (net (code "128") (name "unconnected-(Sc4-PadS)") (class "Default")
      (node (ref "Sc4") (pin "S") (pinfunction "S_S") (pintype "passive"))
    )
    (net (code "129") (name "unconnected-(U1-AREF-Pad98)") (class "Default")
      (node (ref "U1") (pin "98") (pinfunction "AREF_98") (pintype "power_in+no_connect"))
    )
    (net (code "130") (name "unconnected-(U1-PB0_(~{SS}{slash}PCINT0)-Pad19)") (class "Default")
      (node (ref "U1") (pin "19") (pinfunction "PB0_(~{SS}/PCINT0)_19") (pintype "bidirectional+no_connect"))
    )
    (net (code "131") (name "unconnected-(U1-PB4_(OC2A{slash}PCINT4)-Pad23)") (class "Default")
      (node (ref "U1") (pin "23") (pinfunction "PB4_(OC2A/PCINT4)_23") (pintype "bidirectional+no_connect"))
    )
    (net (code "132") (name "unconnected-(U1-PB5_(OC1A{slash}PCINT5)-Pad24)") (class "Default")
      (node (ref "U1") (pin "24") (pinfunction "PB5_(OC1A/PCINT5)_24") (pintype "bidirectional+no_connect"))
    )
    (net (code "133") (name "unconnected-(U1-PB6_(OC1B{slash}PCINT6)-Pad25)") (class "Default")
      (node (ref "U1") (pin "25") (pinfunction "PB6_(OC1B/PCINT6)_25") (pintype "bidirectional+no_connect"))
    )
    (net (code "134") (name "unconnected-(U1-PB7_(OC0A{slash}OC1C{slash}PCINT7)-Pad26)") (class "Default")
      (node (ref "U1") (pin "26") (pinfunction "PB7_(OC0A/OC1C/PCINT7)_26") (pintype "bidirectional+no_connect"))
    )
    (net (code "135") (name "unconnected-(U1-PE2_(XCK0{slash}AIN0)-Pad4)") (class "Default")
      (node (ref "U1") (pin "4") (pinfunction "PE2_(XCK0/AIN0)_4") (pintype "bidirectional+no_connect"))
    )
    (net (code "136") (name "unconnected-(U1-PE3_(OC3A{slash}AIN1)-Pad5)") (class "Default")
      (node (ref "U1") (pin "5") (pinfunction "PE3_(OC3A/AIN1)_5") (pintype "bidirectional+no_connect"))
    )
    (net (code "137") (name "unconnected-(U1-PE4_(OC3B{slash}INT4)-Pad6)") (class "Default")
      (node (ref "U1") (pin "6") (pinfunction "PE4_(OC3B/INT4)_6") (pintype "bidirectional+no_connect"))
    )
    (net (code "138") (name "unconnected-(U1-PE5_(OC3C{slash}INT5)-Pad7)") (class "Default")
      (node (ref "U1") (pin "7") (pinfunction "PE5_(OC3C/INT5)_7") (pintype "bidirectional+no_connect"))
    )
    (net (code "139") (name "unconnected-(U1-PE6_(T3{slash}INT6)-Pad8)") (class "Default")
      (node (ref "U1") (pin "8") (pinfunction "PE6_(T3/INT6)_8") (pintype "bidirectional+no_connect"))
    )
    (net (code "140") (name "unconnected-(U1-PE7_(CLKO{slash}ICP3{slash}INT7)-Pad9)") (class "Default")
      (node (ref "U1") (pin "9") (pinfunction "PE7_(CLKO/ICP3/INT7)_9") (pintype "bidirectional+no_connect"))
    )
    (net (code "141") (name "unconnected-(U1-PF0_(ADC0)-Pad97)") (class "Default")
      (node (ref "U1") (pin "97") (pinfunction "PF0_(ADC0)_97") (pintype "bidirectional+no_connect"))
    )
    (net (code "142") (name "unconnected-(U1-PF3_(ADC3)-Pad94)") (class "Default")
      (node (ref "U1") (pin "94") (pinfunction "PF3_(ADC3)_94") (pintype "bidirectional+no_connect"))
    )
    (net (code "143") (name "unconnected-(U1-PF4_(ADC4{slash}TCK)-Pad93)") (class "Default")
      (node (ref "U1") (pin "93") (pinfunction "PF4_(ADC4/TCK)_93") (pintype "bidirectional+no_connect"))
    )
    (net (code "144") (name "unconnected-(U1-PF5_(ADC5{slash}TMS)-Pad92)") (class "Default")
      (node (ref "U1") (pin "92") (pinfunction "PF5_(ADC5/TMS)_92") (pintype "bidirectional+no_connect"))
    )
    (net (code "145") (name "unconnected-(U1-PF6_(ADC6{slash}TDO)-Pad91)") (class "Default")
      (node (ref "U1") (pin "91") (pinfunction "PF6_(ADC6/TDO)_91") (pintype "bidirectional+no_connect"))
    )
    (net (code "146") (name "unconnected-(U1-PF7_(ADC7{slash}TDI)-Pad90)") (class "Default")
      (node (ref "U1") (pin "90") (pinfunction "PF7_(ADC7/TDI)_90") (pintype "bidirectional+no_connect"))
    )
    (net (code "147") (name "unconnected-(U1-PG0_(WR)-Pad51)") (class "Default")
      (node (ref "U1") (pin "51") (pinfunction "PG0_(WR)_51") (pintype "bidirectional+no_connect"))
    )
    (net (code "148") (name "unconnected-(U1-PG1_(RD)-Pad52)") (class "Default")
      (node (ref "U1") (pin "52") (pinfunction "PG1_(RD)_52") (pintype "bidirectional+no_connect"))
    )
    (net (code "149") (name "unconnected-(U1-PG2_(ALE)-Pad70)") (class "Default")
      (node (ref "U1") (pin "70") (pinfunction "PG2_(ALE)_70") (pintype "bidirectional+no_connect"))
    )
    (net (code "150") (name "unconnected-(U1-PG3_(TOSC2)-Pad28)") (class "Default")
      (node (ref "U1") (pin "28") (pinfunction "PG3_(TOSC2)_28") (pintype "bidirectional+no_connect"))
    )
    (net (code "151") (name "unconnected-(U1-PG4_(TOSC1)-Pad29)") (class "Default")
      (node (ref "U1") (pin "29") (pinfunction "PG4_(TOSC1)_29") (pintype "bidirectional+no_connect"))
    )
    (net (code "152") (name "unconnected-(U1-PG5_(OC0B)-Pad1)") (class "Default")
      (node (ref "U1") (pin "1") (pinfunction "PG5_(OC0B)_1") (pintype "bidirectional+no_connect"))
    )
    (net (code "153") (name "unconnected-(U1-PH0_(RXD2)-Pad12)") (class "Default")
      (node (ref "U1") (pin "12") (pinfunction "PH0_(RXD2)_12") (pintype "bidirectional+no_connect"))
    )
    (net (code "154") (name "unconnected-(U1-PH1_(TXD2)-Pad13)") (class "Default")
      (node (ref "U1") (pin "13") (pinfunction "PH1_(TXD2)_13") (pintype "bidirectional+no_connect"))
    )
    (net (code "155") (name "unconnected-(U1-PH2_(XCK2)-Pad14)") (class "Default")
      (node (ref "U1") (pin "14") (pinfunction "PH2_(XCK2)_14") (pintype "bidirectional+no_connect"))
    )
    (net (code "156") (name "unconnected-(U1-PH7_(T4)-Pad27)") (class "Default")
      (node (ref "U1") (pin "27") (pinfunction "PH7_(T4)_27") (pintype "bidirectional+no_connect"))
    )
    (net (code "157") (name "unconnected-(U1-PJ0_(RXD3{slash}PCINT9)-Pad63)") (class "Default")
      (node (ref "U1") (pin "63") (pinfunction "PJ0_(RXD3/PCINT9)_63") (pintype "bidirectional+no_connect"))
    )
    (net (code "158") (name "unconnected-(U1-PJ1_(TXD3{slash}PCINT10)-Pad64)") (class "Default")
      (node (ref "U1") (pin "64") (pinfunction "PJ1_(TXD3/PCINT10)_64") (pintype "bidirectional+no_connect"))
    )
    (net (code "159") (name "unconnected-(U1-PJ2_(XCK3{slash}PCINT11)-Pad65)") (class "Default")
      (node (ref "U1") (pin "65") (pinfunction "PJ2_(XCK3/PCINT11)_65") (pintype "bidirectional+no_connect"))
    )
    (net (code "160") (name "unconnected-(U1-PJ3_(PCINT12)-Pad66)") (class "Default")
      (node (ref "U1") (pin "66") (pinfunction "PJ3_(PCINT12)_66") (pintype "bidirectional+no_connect"))
    )
    (net (code "161") (name "unconnected-(U1-PJ4_(PCINT13)-Pad67)") (class "Default")
      (node (ref "U1") (pin "67") (pinfunction "PJ4_(PCINT13)_67") (pintype "bidirectional+no_connect"))
    )
    (net (code "162") (name "unconnected-(U1-PJ5_(PCINT14)-Pad68)") (class "Default")
      (node (ref "U1") (pin "68") (pinfunction "PJ5_(PCINT14)_68") (pintype "bidirectional+no_connect"))
    )
    (net (code "163") (name "unconnected-(U1-PJ6_(PCINT15)-Pad69)") (class "Default")
      (node (ref "U1") (pin "69") (pinfunction "PJ6_(PCINT15)_69") (pintype "bidirectional+no_connect"))
    )
    (net (code "164") (name "unconnected-(U1-PJ7-Pad79)") (class "Default")
      (node (ref "U1") (pin "79") (pinfunction "PJ7_79") (pintype "bidirectional+no_connect"))
    )
    (net (code "165") (name "unconnected-(U1-PL0_(ICP4)-Pad35)") (class "Default")
      (node (ref "U1") (pin "35") (pinfunction "PL0_(ICP4)_35") (pintype "bidirectional+no_connect"))
    )
    (net (code "166") (name "unconnected-(U1-PL1_(ICP5)-Pad36)") (class "Default")
      (node (ref "U1") (pin "36") (pinfunction "PL1_(ICP5)_36") (pintype "bidirectional+no_connect"))
    )
    (net (code "167") (name "unconnected-(U1-PL2_(T5)-Pad37)") (class "Default")
      (node (ref "U1") (pin "37") (pinfunction "PL2_(T5)_37") (pintype "bidirectional+no_connect"))
    )
    (net (code "168") (name "unconnected-(U1-PL3_(OC5A)-Pad38)") (class "Default")
      (node (ref "U1") (pin "38") (pinfunction "PL3_(OC5A)_38") (pintype "bidirectional+no_connect"))
    )
    (net (code "169") (name "unconnected-(U1-PL4_(OC5B)-Pad39)") (class "Default")
      (node (ref "U1") (pin "39") (pinfunction "PL4_(OC5B)_39") (pintype "bidirectional+no_connect"))
    )
    (net (code "170") (name "unconnected-(U1-PL5_(OC5C)-Pad40)") (class "Default")
      (node (ref "U1") (pin "40") (pinfunction "PL5_(OC5C)_40") (pintype "bidirectional+no_connect"))
    )
    (net (code "171") (name "unconnected-(U1-PL6-Pad41)") (class "Default")
      (node (ref "U1") (pin "41") (pinfunction "PL6_41") (pintype "bidirectional+no_connect"))
    )
    (net (code "172") (name "unconnected-(U1-PL7-Pad42)") (class "Default")
      (node (ref "U1") (pin "42") (pinfunction "PL7_42") (pintype "bidirectional+no_connect"))
    )
  )
)
